# Supplies_Isense.net
KiCad netlist of a schematic drawn in Altium Designer
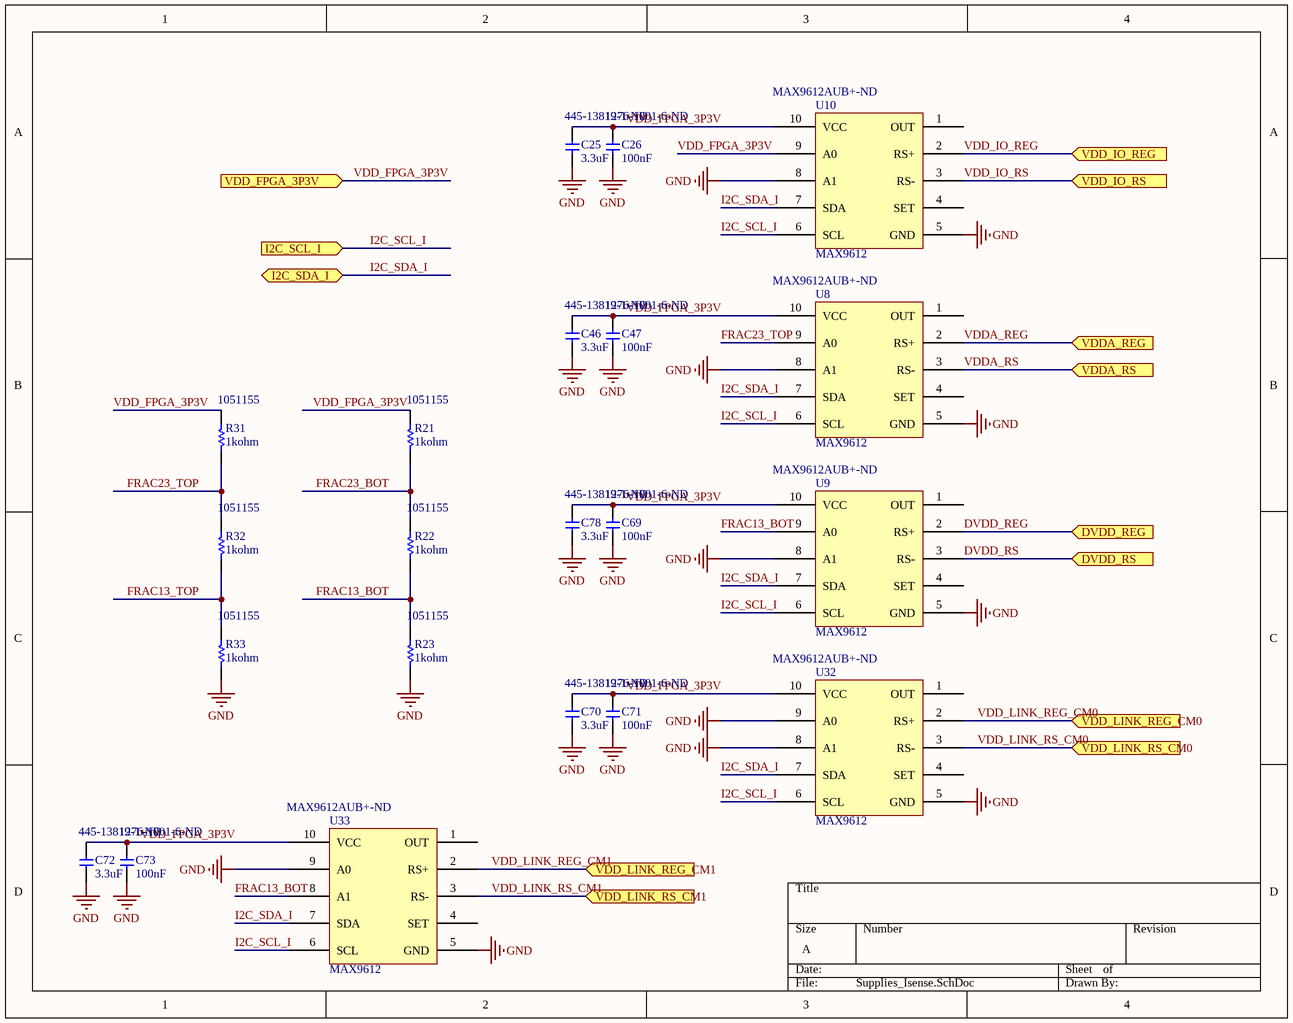
[diagram p0: Supplies_Isense.SchDoc]

(export (version "E")
  (design (tool "Eeschema 10.0.6"))
  (components
    (comp (ref "C25")
      (value "3.3uF")
      (footprint "CAP_0402")
      (description "CAP CER 3.3uF 10% 10V X5R 0402")
      (fields (field (name "MANUFACTURER") "TDK") (field (name "SUPPLIER PART NUMBER 1") "445-13819-1-ND"))
      (libsource (lib "fader2_parts") (part "cap 3p3uF"))
    )
    (comp (ref "C26")
      (value "100nF")
      (footprint "CAP_0402")
      (description "CAP CER 0.1uF 10% 16V X7R 0402")
      (fields
        (field (name "MANUFACTURER") "Samsung Electro-Mechanics")
        (field (name "SUPPLIER PART NUMBER 1") "1276-1001-6-ND")
      )
      (libsource (lib "fader2_parts") (part "cap 100nF"))
    )
    (comp (ref "C46")
      (value "3.3uF")
      (footprint "CAP_0402")
      (description "CAP CER 3.3uF 10% 10V X5R 0402")
      (fields (field (name "MANUFACTURER") "TDK") (field (name "SUPPLIER PART NUMBER 1") "445-13819-1-ND"))
      (libsource (lib "fader2_parts") (part "cap 3p3uF"))
    )
    (comp (ref "C47")
      (value "100nF")
      (footprint "CAP_0402")
      (description "CAP CER 0.1uF 10% 16V X7R 0402")
      (fields
        (field (name "MANUFACTURER") "Samsung Electro-Mechanics")
        (field (name "SUPPLIER PART NUMBER 1") "1276-1001-6-ND")
      )
      (libsource (lib "fader2_parts") (part "cap 100nF"))
    )
    (comp (ref "C69")
      (value "100nF")
      (footprint "CAP_0402")
      (description "CAP CER 0.1uF 10% 16V X7R 0402")
      (fields
        (field (name "MANUFACTURER") "Samsung Electro-Mechanics")
        (field (name "SUPPLIER PART NUMBER 1") "1276-1001-6-ND")
      )
      (libsource (lib "fader2_parts") (part "cap 100nF"))
    )
    (comp (ref "C70")
      (value "3.3uF")
      (footprint "CAP_0402")
      (description "CAP CER 3.3uF 10% 10V X5R 0402")
      (fields (field (name "MANUFACTURER") "TDK") (field (name "SUPPLIER PART NUMBER 1") "445-13819-1-ND"))
      (libsource (lib "fader2_parts") (part "cap 3p3uF"))
    )
    (comp (ref "C71")
      (value "100nF")
      (footprint "CAP_0402")
      (description "CAP CER 0.1uF 10% 16V X7R 0402")
      (fields
        (field (name "MANUFACTURER") "Samsung Electro-Mechanics")
        (field (name "SUPPLIER PART NUMBER 1") "1276-1001-6-ND")
      )
      (libsource (lib "fader2_parts") (part "cap 100nF"))
    )
    (comp (ref "C72")
      (value "3.3uF")
      (footprint "CAP_0402")
      (description "CAP CER 3.3uF 10% 10V X5R 0402")
      (fields (field (name "MANUFACTURER") "TDK") (field (name "SUPPLIER PART NUMBER 1") "445-13819-1-ND"))
      (libsource (lib "fader2_parts") (part "cap 3p3uF"))
    )
    (comp (ref "C73")
      (value "100nF")
      (footprint "CAP_0402")
      (description "CAP CER 0.1uF 10% 16V X7R 0402")
      (fields
        (field (name "MANUFACTURER") "Samsung Electro-Mechanics")
        (field (name "SUPPLIER PART NUMBER 1") "1276-1001-6-ND")
      )
      (libsource (lib "fader2_parts") (part "cap 100nF"))
    )
    (comp (ref "C78")
      (value "3.3uF")
      (footprint "CAP_0402")
      (description "CAP CER 3.3uF 10% 10V X5R 0402")
      (fields (field (name "MANUFACTURER") "TDK") (field (name "SUPPLIER PART NUMBER 1") "445-13819-1-ND"))
      (libsource (lib "fader2_parts") (part "cap 3p3uF"))
    )
    (comp (ref "R21")
      (value "1kohm")
      (footprint "RES_0603")
      (description "RES SMD 1K OHM 1% 1/10W 0603")
      (fields (field (name "MANUFACTURER") "Panasonic") (field (name "SUPPLIER PART NUMBER 1") "1051155"))
      (libsource (lib "fader2_parts") (part "res 1 Kohm"))
    )
    (comp (ref "R22")
      (value "1kohm")
      (footprint "RES_0603")
      (description "RES SMD 1K OHM 1% 1/10W 0603")
      (fields (field (name "MANUFACTURER") "Panasonic") (field (name "SUPPLIER PART NUMBER 1") "1051155"))
      (libsource (lib "fader2_parts") (part "res 1 Kohm"))
    )
    (comp (ref "R23")
      (value "1kohm")
      (footprint "RES_0603")
      (description "RES SMD 1K OHM 1% 1/10W 0603")
      (fields (field (name "MANUFACTURER") "Panasonic") (field (name "SUPPLIER PART NUMBER 1") "1051155"))
      (libsource (lib "fader2_parts") (part "res 1 Kohm"))
    )
    (comp (ref "R31")
      (value "1kohm")
      (footprint "RES_0603")
      (description "RES SMD 1K OHM 1% 1/10W 0603")
      (fields (field (name "MANUFACTURER") "Panasonic") (field (name "SUPPLIER PART NUMBER 1") "1051155"))
      (libsource (lib "fader2_parts") (part "res 1 Kohm"))
    )
    (comp (ref "R32")
      (value "1kohm")
      (footprint "RES_0603")
      (description "RES SMD 1K OHM 1% 1/10W 0603")
      (fields (field (name "MANUFACTURER") "Panasonic") (field (name "SUPPLIER PART NUMBER 1") "1051155"))
      (libsource (lib "fader2_parts") (part "res 1 Kohm"))
    )
    (comp (ref "R33")
      (value "1kohm")
      (footprint "RES_0603")
      (description "RES SMD 1K OHM 1% 1/10W 0603")
      (fields (field (name "MANUFACTURER") "Panasonic") (field (name "SUPPLIER PART NUMBER 1") "1051155"))
      (libsource (lib "fader2_parts") (part "res 1 Kohm"))
    )
    (comp (ref "U8")
      (value "MAX9612")
      (footprint "MAX9612")
      (description "OpAmp ADC")
      (fields (field (name "MANUFACTURER") "Maxim") (field (name "SUPPLIER PART NUMBER 1") "MAX9612AUB+-ND"))
      (libsource (lib "fader2_parts") (part "MAX9612"))
    )
    (comp (ref "U9")
      (value "MAX9612")
      (footprint "MAX9612")
      (description "OpAmp ADC")
      (fields (field (name "MANUFACTURER") "Maxim") (field (name "SUPPLIER PART NUMBER 1") "MAX9612AUB+-ND"))
      (libsource (lib "fader2_parts") (part "MAX9612"))
    )
    (comp (ref "U10")
      (value "MAX9612")
      (footprint "MAX9612")
      (description "OpAmp ADC")
      (fields (field (name "MANUFACTURER") "Maxim") (field (name "SUPPLIER PART NUMBER 1") "MAX9612AUB+-ND"))
      (libsource (lib "fader2_parts") (part "MAX9612"))
    )
    (comp (ref "U32")
      (value "MAX9612")
      (footprint "MAX9612")
      (description "OpAmp ADC")
      (fields (field (name "MANUFACTURER") "Maxim") (field (name "SUPPLIER PART NUMBER 1") "MAX9612AUB+-ND"))
      (libsource (lib "fader2_parts") (part "MAX9612"))
    )
    (comp (ref "U33")
      (value "MAX9612")
      (footprint "MAX9612")
      (description "OpAmp ADC")
      (fields (field (name "MANUFACTURER") "Maxim") (field (name "SUPPLIER PART NUMBER 1") "MAX9612AUB+-ND"))
      (libsource (lib "fader2_parts") (part "MAX9612"))
    )
  )
  (nets
    (net (code "1") (name "/DVDD_REG") (class "Default")
      (node (ref "U9") (pin "2") (pinfunction "RS+_2") (pintype "passive"))
    )
    (net (code "2") (name "/DVDD_RS") (class "Default")
      (node (ref "U9") (pin "3") (pinfunction "RS-_3") (pintype "passive"))
    )
    (net (code "3") (name "/FRAC13_BOT") (class "Default")
      (node (ref "R22") (pin "2") (pinfunction "BOT_2") (pintype "passive"))
      (node (ref "R23") (pin "1") (pinfunction "TOP_1") (pintype "passive"))
      (node (ref "U33") (pin "8") (pinfunction "A1_8") (pintype "passive"))
      (node (ref "U9") (pin "9") (pinfunction "A0_9") (pintype "passive"))
    )
    (net (code "4") (name "/FRAC13_TOP") (class "Default")
      (node (ref "R32") (pin "2") (pinfunction "BOT_2") (pintype "passive"))
      (node (ref "R33") (pin "1") (pinfunction "TOP_1") (pintype "passive"))
    )
    (net (code "5") (name "/FRAC23_BOT") (class "Default")
      (node (ref "R21") (pin "2") (pinfunction "BOT_2") (pintype "passive"))
      (node (ref "R22") (pin "1") (pinfunction "TOP_1") (pintype "passive"))
    )
    (net (code "6") (name "/FRAC23_TOP") (class "Default")
      (node (ref "R31") (pin "2") (pinfunction "BOT_2") (pintype "passive"))
      (node (ref "R32") (pin "1") (pinfunction "TOP_1") (pintype "passive"))
      (node (ref "U8") (pin "9") (pinfunction "A0_9") (pintype "passive"))
    )
    (net (code "7") (name "/I2C_SCL_I") (class "Default")
      (node (ref "U10") (pin "6") (pinfunction "SCL_6") (pintype "passive"))
      (node (ref "U32") (pin "6") (pinfunction "SCL_6") (pintype "passive"))
      (node (ref "U33") (pin "6") (pinfunction "SCL_6") (pintype "passive"))
      (node (ref "U8") (pin "6") (pinfunction "SCL_6") (pintype "passive"))
      (node (ref "U9") (pin "6") (pinfunction "SCL_6") (pintype "passive"))
    )
    (net (code "8") (name "/I2C_SDA_I") (class "Default")
      (node (ref "U10") (pin "7") (pinfunction "SDA_7") (pintype "passive"))
      (node (ref "U32") (pin "7") (pinfunction "SDA_7") (pintype "passive"))
      (node (ref "U33") (pin "7") (pinfunction "SDA_7") (pintype "passive"))
      (node (ref "U8") (pin "7") (pinfunction "SDA_7") (pintype "passive"))
      (node (ref "U9") (pin "7") (pinfunction "SDA_7") (pintype "passive"))
    )
    (net (code "9") (name "/VDDA_REG") (class "Default")
      (node (ref "U8") (pin "2") (pinfunction "RS+_2") (pintype "passive"))
    )
    (net (code "10") (name "/VDDA_RS") (class "Default")
      (node (ref "U8") (pin "3") (pinfunction "RS-_3") (pintype "passive"))
    )
    (net (code "11") (name "/VDD_FPGA_3P3V") (class "Default")
      (node (ref "C25") (pin "1") (pinfunction "1_1") (pintype "passive"))
      (node (ref "C26") (pin "1") (pinfunction "1_1") (pintype "passive"))
      (node (ref "C46") (pin "1") (pinfunction "1_1") (pintype "passive"))
      (node (ref "C47") (pin "1") (pinfunction "1_1") (pintype "passive"))
      (node (ref "C69") (pin "1") (pinfunction "1_1") (pintype "passive"))
      (node (ref "C70") (pin "1") (pinfunction "1_1") (pintype "passive"))
      (node (ref "C71") (pin "1") (pinfunction "1_1") (pintype "passive"))
      (node (ref "C72") (pin "1") (pinfunction "1_1") (pintype "passive"))
      (node (ref "C73") (pin "1") (pinfunction "1_1") (pintype "passive"))
      (node (ref "C78") (pin "1") (pinfunction "1_1") (pintype "passive"))
      (node (ref "R21") (pin "1") (pinfunction "TOP_1") (pintype "passive"))
      (node (ref "R31") (pin "1") (pinfunction "TOP_1") (pintype "passive"))
      (node (ref "U10") (pin "10") (pinfunction "VCC_10") (pintype "passive"))
      (node (ref "U10") (pin "9") (pinfunction "A0_9") (pintype "passive"))
      (node (ref "U32") (pin "10") (pinfunction "VCC_10") (pintype "passive"))
      (node (ref "U33") (pin "10") (pinfunction "VCC_10") (pintype "passive"))
      (node (ref "U8") (pin "10") (pinfunction "VCC_10") (pintype "passive"))
      (node (ref "U9") (pin "10") (pinfunction "VCC_10") (pintype "passive"))
    )
    (net (code "12") (name "/VDD_IO_REG") (class "Default")
      (node (ref "U10") (pin "2") (pinfunction "RS+_2") (pintype "passive"))
    )
    (net (code "13") (name "/VDD_IO_RS") (class "Default")
      (node (ref "U10") (pin "3") (pinfunction "RS-_3") (pintype "passive"))
    )
    (net (code "14") (name "/VDD_LINK_REG_CM0") (class "Default")
      (node (ref "U32") (pin "2") (pinfunction "RS+_2") (pintype "passive"))
    )
    (net (code "15") (name "/VDD_LINK_REG_CM1") (class "Default")
      (node (ref "U33") (pin "2") (pinfunction "RS+_2") (pintype "passive"))
    )
    (net (code "16") (name "/VDD_LINK_RS_CM0") (class "Default")
      (node (ref "U32") (pin "3") (pinfunction "RS-_3") (pintype "passive"))
    )
    (net (code "17") (name "/VDD_LINK_RS_CM1") (class "Default")
      (node (ref "U33") (pin "3") (pinfunction "RS-_3") (pintype "passive"))
    )
    (net (code "18") (name "GND") (class "Default")
      (node (ref "C25") (pin "2") (pinfunction "2_2") (pintype "passive"))
      (node (ref "C26") (pin "2") (pinfunction "2_2") (pintype "passive"))
      (node (ref "C46") (pin "2") (pinfunction "2_2") (pintype "passive"))
      (node (ref "C47") (pin "2") (pinfunction "2_2") (pintype "passive"))
      (node (ref "C69") (pin "2") (pinfunction "2_2") (pintype "passive"))
      (node (ref "C70") (pin "2") (pinfunction "2_2") (pintype "passive"))
      (node (ref "C71") (pin "2") (pinfunction "2_2") (pintype "passive"))
      (node (ref "C72") (pin "2") (pinfunction "2_2") (pintype "passive"))
      (node (ref "C73") (pin "2") (pinfunction "2_2") (pintype "passive"))
      (node (ref "C78") (pin "2") (pinfunction "2_2") (pintype "passive"))
      (node (ref "R23") (pin "2") (pinfunction "BOT_2") (pintype "passive"))
      (node (ref "R33") (pin "2") (pinfunction "BOT_2") (pintype "passive"))
      (node (ref "U10") (pin "5") (pinfunction "GND_5") (pintype "passive"))
      (node (ref "U10") (pin "8") (pinfunction "A1_8") (pintype "passive"))
      (node (ref "U32") (pin "5") (pinfunction "GND_5") (pintype "passive"))
      (node (ref "U32") (pin "8") (pinfunction "A1_8") (pintype "passive"))
      (node (ref "U32") (pin "9") (pinfunction "A0_9") (pintype "passive"))
      (node (ref "U33") (pin "5") (pinfunction "GND_5") (pintype "passive"))
      (node (ref "U33") (pin "9") (pinfunction "A0_9") (pintype "passive"))
      (node (ref "U8") (pin "5") (pinfunction "GND_5") (pintype "passive"))
      (node (ref "U8") (pin "8") (pinfunction "A1_8") (pintype "passive"))
      (node (ref "U9") (pin "5") (pinfunction "GND_5") (pintype "passive"))
      (node (ref "U9") (pin "8") (pinfunction "A1_8") (pintype "passive"))
    )
    (net (code "19") (name "unconnected-(U8-OUT-Pad1)") (class "Default")
      (node (ref "U8") (pin "1") (pinfunction "OUT_1") (pintype "passive"))
    )
    (net (code "20") (name "unconnected-(U8-SET-Pad4)") (class "Default")
      (node (ref "U8") (pin "4") (pinfunction "SET_4") (pintype "passive"))
    )
    (net (code "21") (name "unconnected-(U9-OUT-Pad1)") (class "Default")
      (node (ref "U9") (pin "1") (pinfunction "OUT_1") (pintype "passive"))
    )
    (net (code "22") (name "unconnected-(U9-SET-Pad4)") (class "Default")
      (node (ref "U9") (pin "4") (pinfunction "SET_4") (pintype "passive"))
    )
    (net (code "23") (name "unconnected-(U10-OUT-Pad1)") (class "Default")
      (node (ref "U10") (pin "1") (pinfunction "OUT_1") (pintype "passive"))
    )
    (net (code "24") (name "unconnected-(U10-SET-Pad4)") (class "Default")
      (node (ref "U10") (pin "4") (pinfunction "SET_4") (pintype "passive"))
    )
    (net (code "25") (name "unconnected-(U32-OUT-Pad1)") (class "Default")
      (node (ref "U32") (pin "1") (pinfunction "OUT_1") (pintype "passive"))
    )
    (net (code "26") (name "unconnected-(U32-SET-Pad4)") (class "Default")
      (node (ref "U32") (pin "4") (pinfunction "SET_4") (pintype "passive"))
    )
    (net (code "27") (name "unconnected-(U33-OUT-Pad1)") (class "Default")
      (node (ref "U33") (pin "1") (pinfunction "OUT_1") (pintype "passive"))
    )
    (net (code "28") (name "unconnected-(U33-SET-Pad4)") (class "Default")
      (node (ref "U33") (pin "4") (pinfunction "SET_4") (pintype "passive"))
    )
  )
)
